# oven-controller-v3.net
KiCad netlist of a schematic drawn in EAGLE
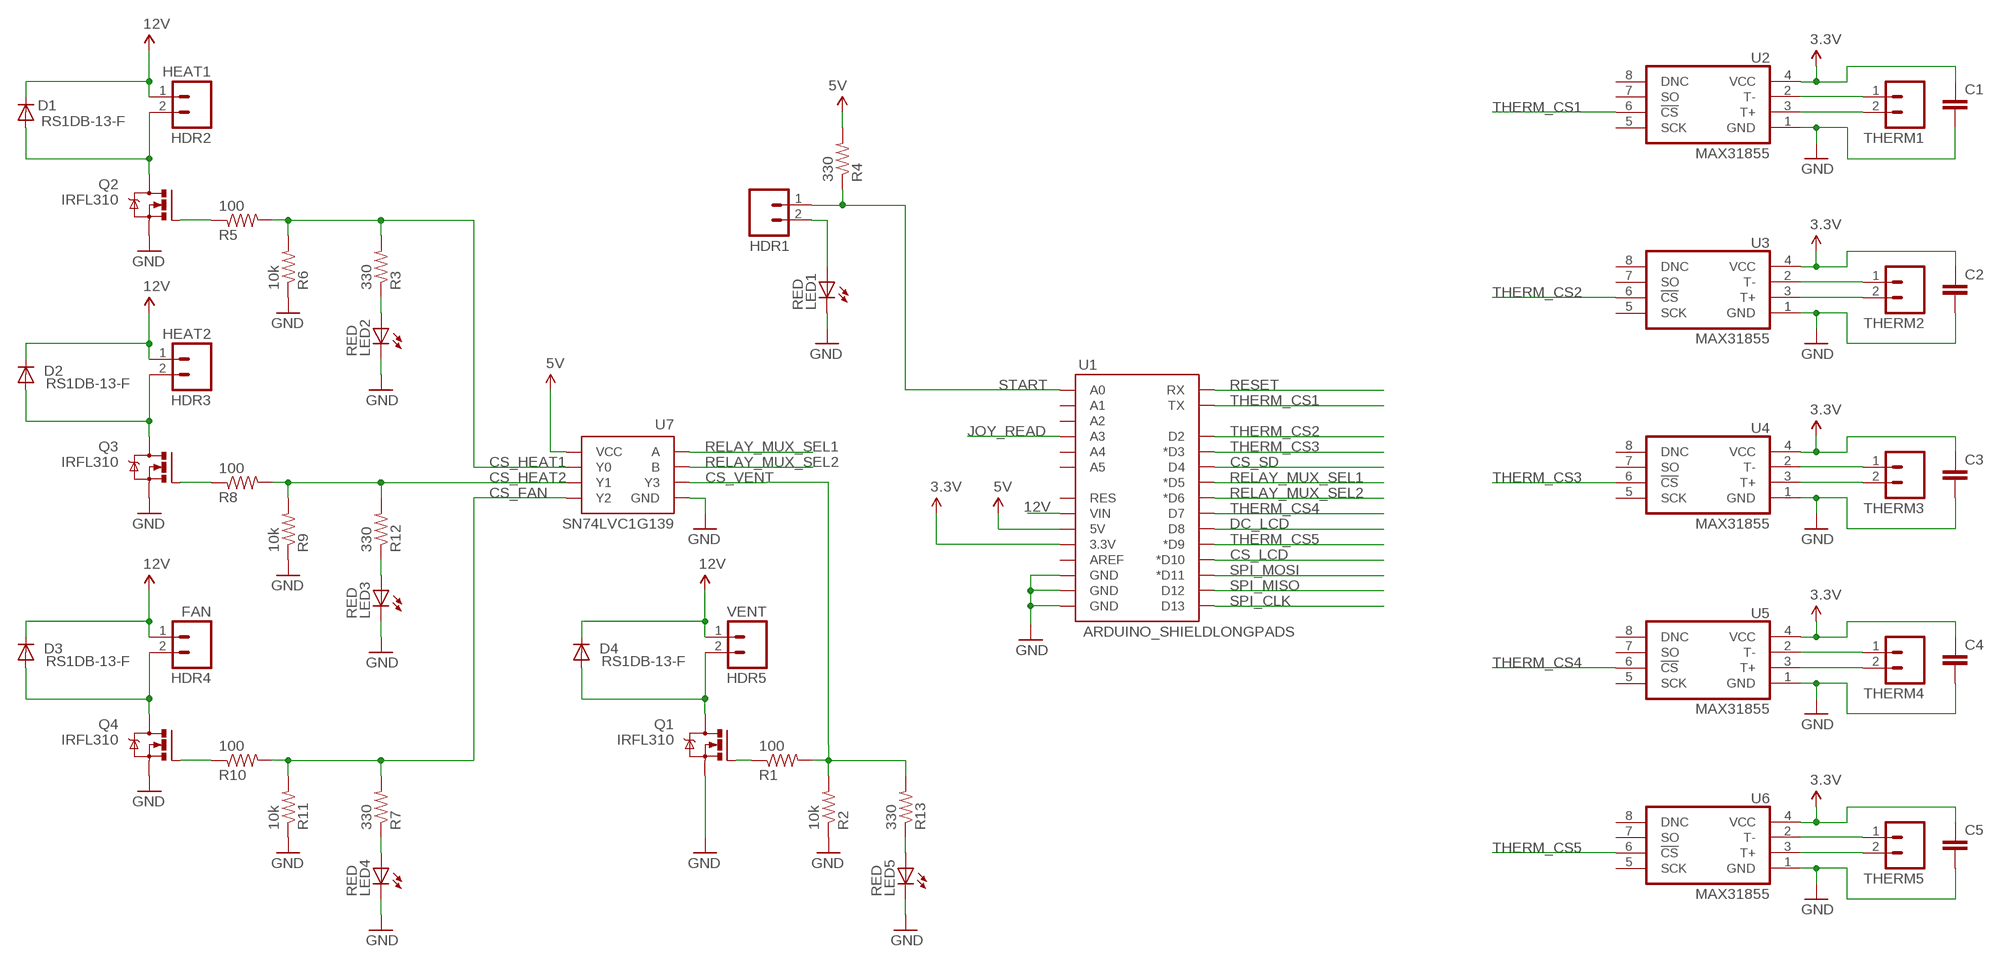
[diagram p0: schematic, sheet 1]

(export (version "E")
  (design (tool "Eeschema 10.0.6"))
  (components
    (comp (ref "C1")
      (value "C-EUC0603K")
      (footprint "eagle-import:C0603K")
      (libsource (lib "eagle-import") (part "C-EUC0603K"))
    )
    (comp (ref "C2")
      (value "C-EUC0603K")
      (footprint "eagle-import:C0603K")
      (libsource (lib "eagle-import") (part "C-EUC0603K"))
    )
    (comp (ref "C3")
      (value "C-EUC0603K")
      (footprint "eagle-import:C0603K")
      (libsource (lib "eagle-import") (part "C-EUC0603K"))
    )
    (comp (ref "C4")
      (value "C-EUC0603K")
      (footprint "eagle-import:C0603K")
      (libsource (lib "eagle-import") (part "C-EUC0603K"))
    )
    (comp (ref "C5")
      (value "C-EUC0603K")
      (footprint "eagle-import:C0603K")
      (libsource (lib "eagle-import") (part "C-EUC0603K"))
    )
    (comp (ref "D1")
      (value "RS1DB-13-F")
      (footprint "eagle-import:SMA-DIODE_ALT")
      (libsource (lib "eagle-import") (part "DIODESMA-ALT"))
    )
    (comp (ref "D2")
      (value "RS1DB-13-F")
      (footprint "eagle-import:SMA-DIODE_ALT")
      (libsource (lib "eagle-import") (part "DIODESMA-ALT"))
    )
    (comp (ref "D3")
      (value "RS1DB-13-F")
      (footprint "eagle-import:SMA-DIODE_ALT")
      (libsource (lib "eagle-import") (part "DIODESMA-ALT"))
    )
    (comp (ref "D4")
      (value "RS1DB-13-F")
      (footprint "eagle-import:SMA-DIODE_ALT")
      (libsource (lib "eagle-import") (part "DIODESMA-ALT"))
    )
    (comp (ref "HDR1")
      (value "M023.5MM_LOCK")
      (footprint "eagle-import:SCREWTERMINAL-3.5MM-2_LOCK")
      (libsource (lib "eagle-import") (part "M023.5MM_LOCK"))
    )
    (comp (ref "HDR2")
      (value "HEAT1")
      (footprint "eagle-import:SCREWTERMINAL-3.5MM-2_LOCK")
      (libsource (lib "eagle-import") (part "M023.5MM_LOCK"))
    )
    (comp (ref "HDR3")
      (value "HEAT2")
      (footprint "eagle-import:SCREWTERMINAL-3.5MM-2_LOCK")
      (libsource (lib "eagle-import") (part "M023.5MM_LOCK"))
    )
    (comp (ref "HDR4")
      (value "FAN")
      (footprint "eagle-import:SCREWTERMINAL-3.5MM-2_LOCK")
      (libsource (lib "eagle-import") (part "M023.5MM_LOCK"))
    )
    (comp (ref "HDR5")
      (value "VENT")
      (footprint "eagle-import:SCREWTERMINAL-3.5MM-2_LOCK")
      (libsource (lib "eagle-import") (part "M023.5MM_LOCK"))
    )
    (comp (ref "LED1")
      (value "RED")
      (footprint "eagle-import:LED-0603")
      (libsource (lib "eagle-import") (part "LED0603"))
    )
    (comp (ref "LED2")
      (value "RED")
      (footprint "eagle-import:LED-0603")
      (libsource (lib "eagle-import") (part "LED0603"))
    )
    (comp (ref "LED3")
      (value "RED")
      (footprint "eagle-import:LED-0603")
      (libsource (lib "eagle-import") (part "LED0603"))
    )
    (comp (ref "LED4")
      (value "RED")
      (footprint "eagle-import:LED-0603")
      (libsource (lib "eagle-import") (part "LED0603"))
    )
    (comp (ref "LED5")
      (value "RED")
      (footprint "eagle-import:LED-0603")
      (libsource (lib "eagle-import") (part "LED0603"))
    )
    (comp (ref "Q1")
      (value "IRFL310")
      (footprint "eagle-import:TO220BV")
      (libsource (lib "eagle-import") (part "IRF520"))
    )
    (comp (ref "Q2")
      (value "IRFL310")
      (footprint "eagle-import:TO220BV")
      (libsource (lib "eagle-import") (part "IRF520"))
    )
    (comp (ref "Q3")
      (value "IRFL310")
      (footprint "eagle-import:TO220BV")
      (libsource (lib "eagle-import") (part "IRF520"))
    )
    (comp (ref "Q4")
      (value "IRFL310")
      (footprint "eagle-import:TO220BV")
      (libsource (lib "eagle-import") (part "IRF520"))
    )
    (comp (ref "R1")
      (value "100")
      (footprint "eagle-import:0603-C-NOSILK")
      (libsource (lib "eagle-import") (part "R-US_0603-C-NOSILK"))
    )
    (comp (ref "R2")
      (value "10k")
      (footprint "eagle-import:0603-C-NOSILK")
      (libsource (lib "eagle-import") (part "R-US_0603-C-NOSILK"))
    )
    (comp (ref "R3")
      (value "330")
      (footprint "eagle-import:0603-C-NOSILK")
      (libsource (lib "eagle-import") (part "R-US_0603-C-NOSILK"))
    )
    (comp (ref "R4")
      (value "330")
      (footprint "eagle-import:0603-C-NOSILK")
      (libsource (lib "eagle-import") (part "R-US_0603-C-NOSILK"))
    )
    (comp (ref "R5")
      (value "100")
      (footprint "eagle-import:0603-C-NOSILK")
      (libsource (lib "eagle-import") (part "R-US_0603-C-NOSILK"))
    )
    (comp (ref "R6")
      (value "10k")
      (footprint "eagle-import:0603-C-NOSILK")
      (libsource (lib "eagle-import") (part "R-US_0603-C-NOSILK"))
    )
    (comp (ref "R7")
      (value "330")
      (footprint "eagle-import:0603-C-NOSILK")
      (libsource (lib "eagle-import") (part "R-US_0603-C-NOSILK"))
    )
    (comp (ref "R8")
      (value "100")
      (footprint "eagle-import:0603-C-NOSILK")
      (libsource (lib "eagle-import") (part "R-US_0603-C-NOSILK"))
    )
    (comp (ref "R9")
      (value "10k")
      (footprint "eagle-import:0603-C-NOSILK")
      (libsource (lib "eagle-import") (part "R-US_0603-C-NOSILK"))
    )
    (comp (ref "R10")
      (value "100")
      (footprint "eagle-import:0603-C-NOSILK")
      (libsource (lib "eagle-import") (part "R-US_0603-C-NOSILK"))
    )
    (comp (ref "R11")
      (value "10k")
      (footprint "eagle-import:0603-C-NOSILK")
      (libsource (lib "eagle-import") (part "R-US_0603-C-NOSILK"))
    )
    (comp (ref "R12")
      (value "330")
      (footprint "eagle-import:0603-C-NOSILK")
      (libsource (lib "eagle-import") (part "R-US_0603-C-NOSILK"))
    )
    (comp (ref "R13")
      (value "330")
      (footprint "eagle-import:0603-C-NOSILK")
      (libsource (lib "eagle-import") (part "R-US_0603-C-NOSILK"))
    )
    (comp (ref "THERM1")
      (value "M023.5MM_LOCK")
      (footprint "eagle-import:SCREWTERMINAL-3.5MM-2_LOCK")
      (libsource (lib "eagle-import") (part "M023.5MM_LOCK"))
    )
    (comp (ref "THERM2")
      (value "M023.5MM_LOCK")
      (footprint "eagle-import:SCREWTERMINAL-3.5MM-2_LOCK")
      (libsource (lib "eagle-import") (part "M023.5MM_LOCK"))
    )
    (comp (ref "THERM3")
      (value "M023.5MM_LOCK")
      (footprint "eagle-import:SCREWTERMINAL-3.5MM-2_LOCK")
      (libsource (lib "eagle-import") (part "M023.5MM_LOCK"))
    )
    (comp (ref "THERM4")
      (value "M023.5MM_LOCK")
      (footprint "eagle-import:SCREWTERMINAL-3.5MM-2_LOCK")
      (libsource (lib "eagle-import") (part "M023.5MM_LOCK"))
    )
    (comp (ref "THERM5")
      (value "M023.5MM_LOCK")
      (footprint "eagle-import:SCREWTERMINAL-3.5MM-2_LOCK")
      (libsource (lib "eagle-import") (part "M023.5MM_LOCK"))
    )
    (comp (ref "U1")
      (value "ARDUINO_SHIELDLONGPADS")
      (footprint "eagle-import:DUEMILANOVE_SHIELD_LONGPADS")
      (libsource (lib "eagle-import") (part "ARDUINO_SHIELDLONGPADS"))
    )
    (comp (ref "U2")
      (value "MAX31855")
      (footprint "eagle-import:SO-8")
      (libsource (lib "eagle-import") (part "IC_MAX31855-SO-8"))
    )
    (comp (ref "U3")
      (value "MAX31855")
      (footprint "eagle-import:SO-8")
      (libsource (lib "eagle-import") (part "IC_MAX31855-SO-8"))
    )
    (comp (ref "U4")
      (value "MAX31855")
      (footprint "eagle-import:SO-8")
      (libsource (lib "eagle-import") (part "IC_MAX31855-SO-8"))
    )
    (comp (ref "U5")
      (value "MAX31855")
      (footprint "eagle-import:SO-8")
      (libsource (lib "eagle-import") (part "IC_MAX31855-SO-8"))
    )
    (comp (ref "U6")
      (value "MAX31855")
      (footprint "eagle-import:SO-8")
      (libsource (lib "eagle-import") (part "IC_MAX31855-SO-8"))
    )
    (comp (ref "U7")
      (value "SN74LVC1G139")
      (footprint "eagle-import:8LSSOP")
      (libsource (lib "eagle-import") (part "SN74LVC1G139"))
    )
  )
  (nets
    (net (code "1") (name "/CS_FAN") (class "Default")
      (node (ref "R10") (pin "2") (pinfunction "2_2") (pintype "passive"))
      (node (ref "R11") (pin "2") (pinfunction "2_2") (pintype "passive"))
      (node (ref "R7") (pin "2") (pinfunction "2_2") (pintype "passive"))
      (node (ref "U7") (pin "P$5") (pinfunction "Y2_P$5") (pintype "bidirectional"))
    )
    (net (code "2") (name "/CS_HEAT1") (class "Default")
      (node (ref "R3") (pin "2") (pinfunction "2_2") (pintype "passive"))
      (node (ref "R5") (pin "2") (pinfunction "2_2") (pintype "passive"))
      (node (ref "R6") (pin "2") (pinfunction "2_2") (pintype "passive"))
      (node (ref "U7") (pin "P$7") (pinfunction "Y0_P$7") (pintype "power_in"))
    )
    (net (code "3") (name "/CS_HEAT2") (class "Default")
      (node (ref "R12") (pin "2") (pinfunction "2_2") (pintype "passive"))
      (node (ref "R8") (pin "2") (pinfunction "2_2") (pintype "passive"))
      (node (ref "R9") (pin "2") (pinfunction "2_2") (pintype "passive"))
      (node (ref "U7") (pin "P$6") (pinfunction "Y1_P$6") (pintype "bidirectional"))
    )
    (net (code "4") (name "/CS_LCD") (class "Default")
      (node (ref "U1") (pin "D10") (pinfunction "*D10_D10") (pintype "bidirectional"))
    )
    (net (code "5") (name "/CS_SD") (class "Default")
      (node (ref "U1") (pin "D4") (pinfunction "D4_D4") (pintype "bidirectional"))
    )
    (net (code "6") (name "/CS_VENT") (class "Default")
      (node (ref "R1") (pin "2") (pinfunction "2_2") (pintype "passive"))
      (node (ref "R13") (pin "2") (pinfunction "2_2") (pintype "passive"))
      (node (ref "R2") (pin "2") (pinfunction "2_2") (pintype "passive"))
      (node (ref "U7") (pin "P$3") (pinfunction "Y3_P$3") (pintype "bidirectional"))
    )
    (net (code "7") (name "/DC_LCD") (class "Default")
      (node (ref "U1") (pin "D8") (pinfunction "D8_D8") (pintype "bidirectional"))
    )
    (net (code "8") (name "/JOY_READ") (class "Default")
      (node (ref "U1") (pin "A3") (pinfunction "A3_A3") (pintype "bidirectional"))
    )
    (net (code "9") (name "/RELAY_MUX_SEL1") (class "Default")
      (node (ref "U1") (pin "D5") (pinfunction "*D5_D5") (pintype "bidirectional"))
      (node (ref "U7") (pin "P$1") (pinfunction "A_P$1") (pintype "bidirectional"))
    )
    (net (code "10") (name "/RELAY_MUX_SEL2") (class "Default")
      (node (ref "U1") (pin "D6") (pinfunction "*D6_D6") (pintype "bidirectional"))
      (node (ref "U7") (pin "P$2") (pinfunction "B_P$2") (pintype "power_in"))
    )
    (net (code "11") (name "/RESET") (class "Default")
      (node (ref "U1") (pin "RX") (pinfunction "RX_RX") (pintype "bidirectional"))
    )
    (net (code "12") (name "/SPI_CLK") (class "Default")
      (node (ref "U1") (pin "D13") (pinfunction "D13_D13") (pintype "bidirectional"))
    )
    (net (code "13") (name "/SPI_MISO") (class "Default")
      (node (ref "U1") (pin "D12") (pinfunction "D12_D12") (pintype "bidirectional"))
    )
    (net (code "14") (name "/SPI_MOSI") (class "Default")
      (node (ref "U1") (pin "D11") (pinfunction "*D11_D11") (pintype "bidirectional"))
    )
    (net (code "15") (name "/START") (class "Default")
      (node (ref "HDR1") (pin "1") (pinfunction "1_1") (pintype "passive"))
      (node (ref "R4") (pin "1") (pinfunction "1_1") (pintype "passive"))
      (node (ref "U1") (pin "A0") (pinfunction "A0_A0") (pintype "bidirectional"))
    )
    (net (code "16") (name "/THERM_CS1") (class "Default")
      (node (ref "U1") (pin "TX") (pinfunction "TX_TX") (pintype "bidirectional"))
      (node (ref "U2") (pin "6") (pinfunction "~{CS}_6") (pintype "input"))
    )
    (net (code "17") (name "/THERM_CS2") (class "Default")
      (node (ref "U1") (pin "D2") (pinfunction "D2_D2") (pintype "bidirectional"))
      (node (ref "U3") (pin "6") (pinfunction "~{CS}_6") (pintype "input"))
    )
    (net (code "18") (name "/THERM_CS3") (class "Default")
      (node (ref "U1") (pin "D3") (pinfunction "*D3_D3") (pintype "bidirectional"))
      (node (ref "U4") (pin "6") (pinfunction "~{CS}_6") (pintype "input"))
    )
    (net (code "19") (name "/THERM_CS4") (class "Default")
      (node (ref "U1") (pin "D7") (pinfunction "D7_D7") (pintype "bidirectional"))
      (node (ref "U5") (pin "6") (pinfunction "~{CS}_6") (pintype "input"))
    )
    (net (code "20") (name "/THERM_CS5") (class "Default")
      (node (ref "U1") (pin "D9") (pinfunction "*D9_D9") (pintype "bidirectional"))
      (node (ref "U6") (pin "6") (pinfunction "~{CS}_6") (pintype "input"))
    )
    (net (code "21") (name "3.3V") (class "Default")
      (node (ref "C1") (pin "1") (pinfunction "1_1") (pintype "passive"))
      (node (ref "C2") (pin "1") (pinfunction "1_1") (pintype "passive"))
      (node (ref "C3") (pin "1") (pinfunction "1_1") (pintype "passive"))
      (node (ref "C4") (pin "1") (pinfunction "1_1") (pintype "passive"))
      (node (ref "C5") (pin "1") (pinfunction "1_1") (pintype "passive"))
      (node (ref "U1") (pin "3.3V") (pinfunction "3.3V_3.3V") (pintype "bidirectional"))
      (node (ref "U2") (pin "4") (pinfunction "VCC_4") (pintype "power_in"))
      (node (ref "U3") (pin "4") (pinfunction "VCC_4") (pintype "power_in"))
      (node (ref "U4") (pin "4") (pinfunction "VCC_4") (pintype "power_in"))
      (node (ref "U5") (pin "4") (pinfunction "VCC_4") (pintype "power_in"))
      (node (ref "U6") (pin "4") (pinfunction "VCC_4") (pintype "power_in"))
    )
    (net (code "22") (name "5V") (class "Default")
      (node (ref "R4") (pin "2") (pinfunction "2_2") (pintype "passive"))
      (node (ref "U1") (pin "5V") (pinfunction "5V_5V") (pintype "bidirectional"))
      (node (ref "U7") (pin "P$8") (pinfunction "VCC_P$8") (pintype "bidirectional"))
    )
    (net (code "23") (name "12V") (class "Default")
      (node (ref "D1") (pin "C") (pinfunction "C_C") (pintype "passive"))
      (node (ref "D2") (pin "C") (pinfunction "C_C") (pintype "passive"))
      (node (ref "D3") (pin "C") (pinfunction "C_C") (pintype "passive"))
      (node (ref "D4") (pin "C") (pinfunction "C_C") (pintype "passive"))
      (node (ref "HDR2") (pin "1") (pinfunction "1_1") (pintype "passive"))
      (node (ref "HDR3") (pin "1") (pinfunction "1_1") (pintype "passive"))
      (node (ref "HDR4") (pin "1") (pinfunction "1_1") (pintype "passive"))
      (node (ref "HDR5") (pin "1") (pinfunction "1_1") (pintype "passive"))
      (node (ref "U1") (pin "VIN") (pinfunction "VIN_VIN") (pintype "bidirectional"))
    )
    (net (code "24") (name "GND") (class "Default")
      (node (ref "C1") (pin "2") (pinfunction "2_2") (pintype "passive"))
      (node (ref "C2") (pin "2") (pinfunction "2_2") (pintype "passive"))
      (node (ref "C3") (pin "2") (pinfunction "2_2") (pintype "passive"))
      (node (ref "C4") (pin "2") (pinfunction "2_2") (pintype "passive"))
      (node (ref "C5") (pin "2") (pinfunction "2_2") (pintype "passive"))
      (node (ref "LED1") (pin "C") (pinfunction "C_C") (pintype "passive"))
      (node (ref "LED2") (pin "C") (pinfunction "C_C") (pintype "passive"))
      (node (ref "LED3") (pin "C") (pinfunction "C_C") (pintype "passive"))
      (node (ref "LED4") (pin "C") (pinfunction "C_C") (pintype "passive"))
      (node (ref "LED5") (pin "C") (pinfunction "C_C") (pintype "passive"))
      (node (ref "Q1") (pin "S") (pinfunction "S_S") (pintype "passive"))
      (node (ref "Q2") (pin "S") (pinfunction "S_S") (pintype "passive"))
      (node (ref "Q3") (pin "S") (pinfunction "S_S") (pintype "passive"))
      (node (ref "Q4") (pin "S") (pinfunction "S_S") (pintype "passive"))
      (node (ref "R11") (pin "1") (pinfunction "1_1") (pintype "passive"))
      (node (ref "R2") (pin "1") (pinfunction "1_1") (pintype "passive"))
      (node (ref "R6") (pin "1") (pinfunction "1_1") (pintype "passive"))
      (node (ref "R9") (pin "1") (pinfunction "1_1") (pintype "passive"))
      (node (ref "U1") (pin "GND@0") (pinfunction "GND_GND@0") (pintype "bidirectional"))
      (node (ref "U1") (pin "GND@1") (pinfunction "GND_GND@1") (pintype "bidirectional"))
      (node (ref "U1") (pin "GND@2") (pinfunction "GND_GND@2") (pintype "bidirectional"))
      (node (ref "U2") (pin "1") (pinfunction "GND_1") (pintype "power_in"))
      (node (ref "U3") (pin "1") (pinfunction "GND_1") (pintype "power_in"))
      (node (ref "U4") (pin "1") (pinfunction "GND_1") (pintype "power_in"))
      (node (ref "U5") (pin "1") (pinfunction "GND_1") (pintype "power_in"))
      (node (ref "U6") (pin "1") (pinfunction "GND_1") (pintype "power_in"))
      (node (ref "U7") (pin "P$4") (pinfunction "GND_P$4") (pintype "bidirectional"))
    )
    (net (code "25") (name "Net-(D1-PadA)") (class "Default")
      (node (ref "D1") (pin "A") (pinfunction "A_A") (pintype "passive"))
      (node (ref "HDR2") (pin "2") (pinfunction "2_2") (pintype "passive"))
      (node (ref "Q2") (pin "D") (pinfunction "D_D") (pintype "passive"))
    )
    (net (code "26") (name "Net-(D2-PadA)") (class "Default")
      (node (ref "D2") (pin "A") (pinfunction "A_A") (pintype "passive"))
      (node (ref "HDR3") (pin "2") (pinfunction "2_2") (pintype "passive"))
      (node (ref "Q3") (pin "D") (pinfunction "D_D") (pintype "passive"))
    )
    (net (code "27") (name "Net-(D3-PadA)") (class "Default")
      (node (ref "D3") (pin "A") (pinfunction "A_A") (pintype "passive"))
      (node (ref "HDR4") (pin "2") (pinfunction "2_2") (pintype "passive"))
      (node (ref "Q4") (pin "D") (pinfunction "D_D") (pintype "passive"))
    )
    (net (code "28") (name "Net-(D4-PadA)") (class "Default")
      (node (ref "D4") (pin "A") (pinfunction "A_A") (pintype "passive"))
      (node (ref "HDR5") (pin "2") (pinfunction "2_2") (pintype "passive"))
      (node (ref "Q1") (pin "D") (pinfunction "D_D") (pintype "passive"))
    )
    (net (code "29") (name "Net-(HDR1-Pad2)") (class "Default")
      (node (ref "HDR1") (pin "2") (pinfunction "2_2") (pintype "passive"))
      (node (ref "LED1") (pin "A") (pinfunction "A_A") (pintype "passive"))
    )
    (net (code "30") (name "Net-(LED2-PadA)") (class "Default")
      (node (ref "LED2") (pin "A") (pinfunction "A_A") (pintype "passive"))
      (node (ref "R3") (pin "1") (pinfunction "1_1") (pintype "passive"))
    )
    (net (code "31") (name "Net-(LED3-PadA)") (class "Default")
      (node (ref "LED3") (pin "A") (pinfunction "A_A") (pintype "passive"))
      (node (ref "R12") (pin "1") (pinfunction "1_1") (pintype "passive"))
    )
    (net (code "32") (name "Net-(LED4-PadA)") (class "Default")
      (node (ref "LED4") (pin "A") (pinfunction "A_A") (pintype "passive"))
      (node (ref "R7") (pin "1") (pinfunction "1_1") (pintype "passive"))
    )
    (net (code "33") (name "Net-(LED5-PadA)") (class "Default")
      (node (ref "LED5") (pin "A") (pinfunction "A_A") (pintype "passive"))
      (node (ref "R13") (pin "1") (pinfunction "1_1") (pintype "passive"))
    )
    (net (code "34") (name "Net-(Q1-PadG)") (class "Default")
      (node (ref "Q1") (pin "G") (pinfunction "G_G") (pintype "passive"))
      (node (ref "R1") (pin "1") (pinfunction "1_1") (pintype "passive"))
    )
    (net (code "35") (name "Net-(Q2-PadG)") (class "Default")
      (node (ref "Q2") (pin "G") (pinfunction "G_G") (pintype "passive"))
      (node (ref "R5") (pin "1") (pinfunction "1_1") (pintype "passive"))
    )
    (net (code "36") (name "Net-(Q3-PadG)") (class "Default")
      (node (ref "Q3") (pin "G") (pinfunction "G_G") (pintype "passive"))
      (node (ref "R8") (pin "1") (pinfunction "1_1") (pintype "passive"))
    )
    (net (code "37") (name "Net-(Q4-PadG)") (class "Default")
      (node (ref "Q4") (pin "G") (pinfunction "G_G") (pintype "passive"))
      (node (ref "R10") (pin "1") (pinfunction "1_1") (pintype "passive"))
    )
    (net (code "38") (name "Net-(U2-T+)") (class "Default")
      (node (ref "THERM1") (pin "2") (pinfunction "2_2") (pintype "passive"))
      (node (ref "U2") (pin "3") (pinfunction "T+_3") (pintype "input"))
    )
    (net (code "39") (name "Net-(U2-T-)") (class "Default")
      (node (ref "THERM1") (pin "1") (pinfunction "1_1") (pintype "passive"))
      (node (ref "U2") (pin "2") (pinfunction "T-_2") (pintype "input"))
    )
    (net (code "40") (name "Net-(U3-T+)") (class "Default")
      (node (ref "THERM2") (pin "2") (pinfunction "2_2") (pintype "passive"))
      (node (ref "U3") (pin "3") (pinfunction "T+_3") (pintype "input"))
    )
    (net (code "41") (name "Net-(U3-T-)") (class "Default")
      (node (ref "THERM2") (pin "1") (pinfunction "1_1") (pintype "passive"))
      (node (ref "U3") (pin "2") (pinfunction "T-_2") (pintype "input"))
    )
    (net (code "42") (name "Net-(U4-T+)") (class "Default")
      (node (ref "THERM3") (pin "2") (pinfunction "2_2") (pintype "passive"))
      (node (ref "U4") (pin "3") (pinfunction "T+_3") (pintype "input"))
    )
    (net (code "43") (name "Net-(U4-T-)") (class "Default")
      (node (ref "THERM3") (pin "1") (pinfunction "1_1") (pintype "passive"))
      (node (ref "U4") (pin "2") (pinfunction "T-_2") (pintype "input"))
    )
    (net (code "44") (name "Net-(U5-T+)") (class "Default")
      (node (ref "THERM4") (pin "2") (pinfunction "2_2") (pintype "passive"))
      (node (ref "U5") (pin "3") (pinfunction "T+_3") (pintype "input"))
    )
    (net (code "45") (name "Net-(U5-T-)") (class "Default")
      (node (ref "THERM4") (pin "1") (pinfunction "1_1") (pintype "passive"))
      (node (ref "U5") (pin "2") (pinfunction "T-_2") (pintype "input"))
    )
    (net (code "46") (name "Net-(U6-T+)") (class "Default")
      (node (ref "THERM5") (pin "2") (pinfunction "2_2") (pintype "passive"))
      (node (ref "U6") (pin "3") (pinfunction "T+_3") (pintype "input"))
    )
    (net (code "47") (name "Net-(U6-T-)") (class "Default")
      (node (ref "THERM5") (pin "1") (pinfunction "1_1") (pintype "passive"))
      (node (ref "U6") (pin "2") (pinfunction "T-_2") (pintype "input"))
    )
    (net (code "48") (name "unconnected-(U1-PadA1)") (class "Default")
      (node (ref "U1") (pin "A1") (pinfunction "A1_A1") (pintype "bidirectional"))
    )
    (net (code "49") (name "unconnected-(U1-PadA2)") (class "Default")
      (node (ref "U1") (pin "A2") (pinfunction "A2_A2") (pintype "bidirectional"))
    )
    (net (code "50") (name "unconnected-(U1-PadA4)") (class "Default")
      (node (ref "U1") (pin "A4") (pinfunction "A4_A4") (pintype "bidirectional"))
    )
    (net (code "51") (name "unconnected-(U1-PadA5)") (class "Default")
      (node (ref "U1") (pin "A5") (pinfunction "A5_A5") (pintype "bidirectional"))
    )
    (net (code "52") (name "unconnected-(U1-PadAREF)") (class "Default")
      (node (ref "U1") (pin "AREF") (pinfunction "AREF_AREF") (pintype "bidirectional"))
    )
    (net (code "53") (name "unconnected-(U1-PadRES)") (class "Default")
      (node (ref "U1") (pin "RES") (pinfunction "RES_RES") (pintype "bidirectional"))
    )
    (net (code "54") (name "unconnected-(U2-DNC-Pad8)") (class "Default")
      (node (ref "U2") (pin "8") (pinfunction "DNC_8") (pintype "no_connect"))
    )
    (net (code "55") (name "unconnected-(U2-SCK-Pad5)") (class "Default")
      (node (ref "U2") (pin "5") (pinfunction "SCK_5") (pintype "input"))
    )
    (net (code "56") (name "unconnected-(U2-SO-Pad7)") (class "Default")
      (node (ref "U2") (pin "7") (pinfunction "SO_7") (pintype "output"))
    )
    (net (code "57") (name "unconnected-(U3-DNC-Pad8)") (class "Default")
      (node (ref "U3") (pin "8") (pinfunction "DNC_8") (pintype "no_connect"))
    )
    (net (code "58") (name "unconnected-(U3-SCK-Pad5)") (class "Default")
      (node (ref "U3") (pin "5") (pinfunction "SCK_5") (pintype "input"))
    )
    (net (code "59") (name "unconnected-(U3-SO-Pad7)") (class "Default")
      (node (ref "U3") (pin "7") (pinfunction "SO_7") (pintype "output"))
    )
    (net (code "60") (name "unconnected-(U4-DNC-Pad8)") (class "Default")
      (node (ref "U4") (pin "8") (pinfunction "DNC_8") (pintype "no_connect"))
    )
    (net (code "61") (name "unconnected-(U4-SCK-Pad5)") (class "Default")
      (node (ref "U4") (pin "5") (pinfunction "SCK_5") (pintype "input"))
    )
    (net (code "62") (name "unconnected-(U4-SO-Pad7)") (class "Default")
      (node (ref "U4") (pin "7") (pinfunction "SO_7") (pintype "output"))
    )
    (net (code "63") (name "unconnected-(U5-DNC-Pad8)") (class "Default")
      (node (ref "U5") (pin "8") (pinfunction "DNC_8") (pintype "no_connect"))
    )
    (net (code "64") (name "unconnected-(U5-SCK-Pad5)") (class "Default")
      (node (ref "U5") (pin "5") (pinfunction "SCK_5") (pintype "input"))
    )
    (net (code "65") (name "unconnected-(U5-SO-Pad7)") (class "Default")
      (node (ref "U5") (pin "7") (pinfunction "SO_7") (pintype "output"))
    )
    (net (code "66") (name "unconnected-(U6-DNC-Pad8)") (class "Default")
      (node (ref "U6") (pin "8") (pinfunction "DNC_8") (pintype "no_connect"))
    )
    (net (code "67") (name "unconnected-(U6-SCK-Pad5)") (class "Default")
      (node (ref "U6") (pin "5") (pinfunction "SCK_5") (pintype "input"))
    )
    (net (code "68") (name "unconnected-(U6-SO-Pad7)") (class "Default")
      (node (ref "U6") (pin "7") (pinfunction "SO_7") (pintype "output"))
    )
  )
)
